# PowerModule.net
KiCad netlist of a schematic drawn in EAGLE
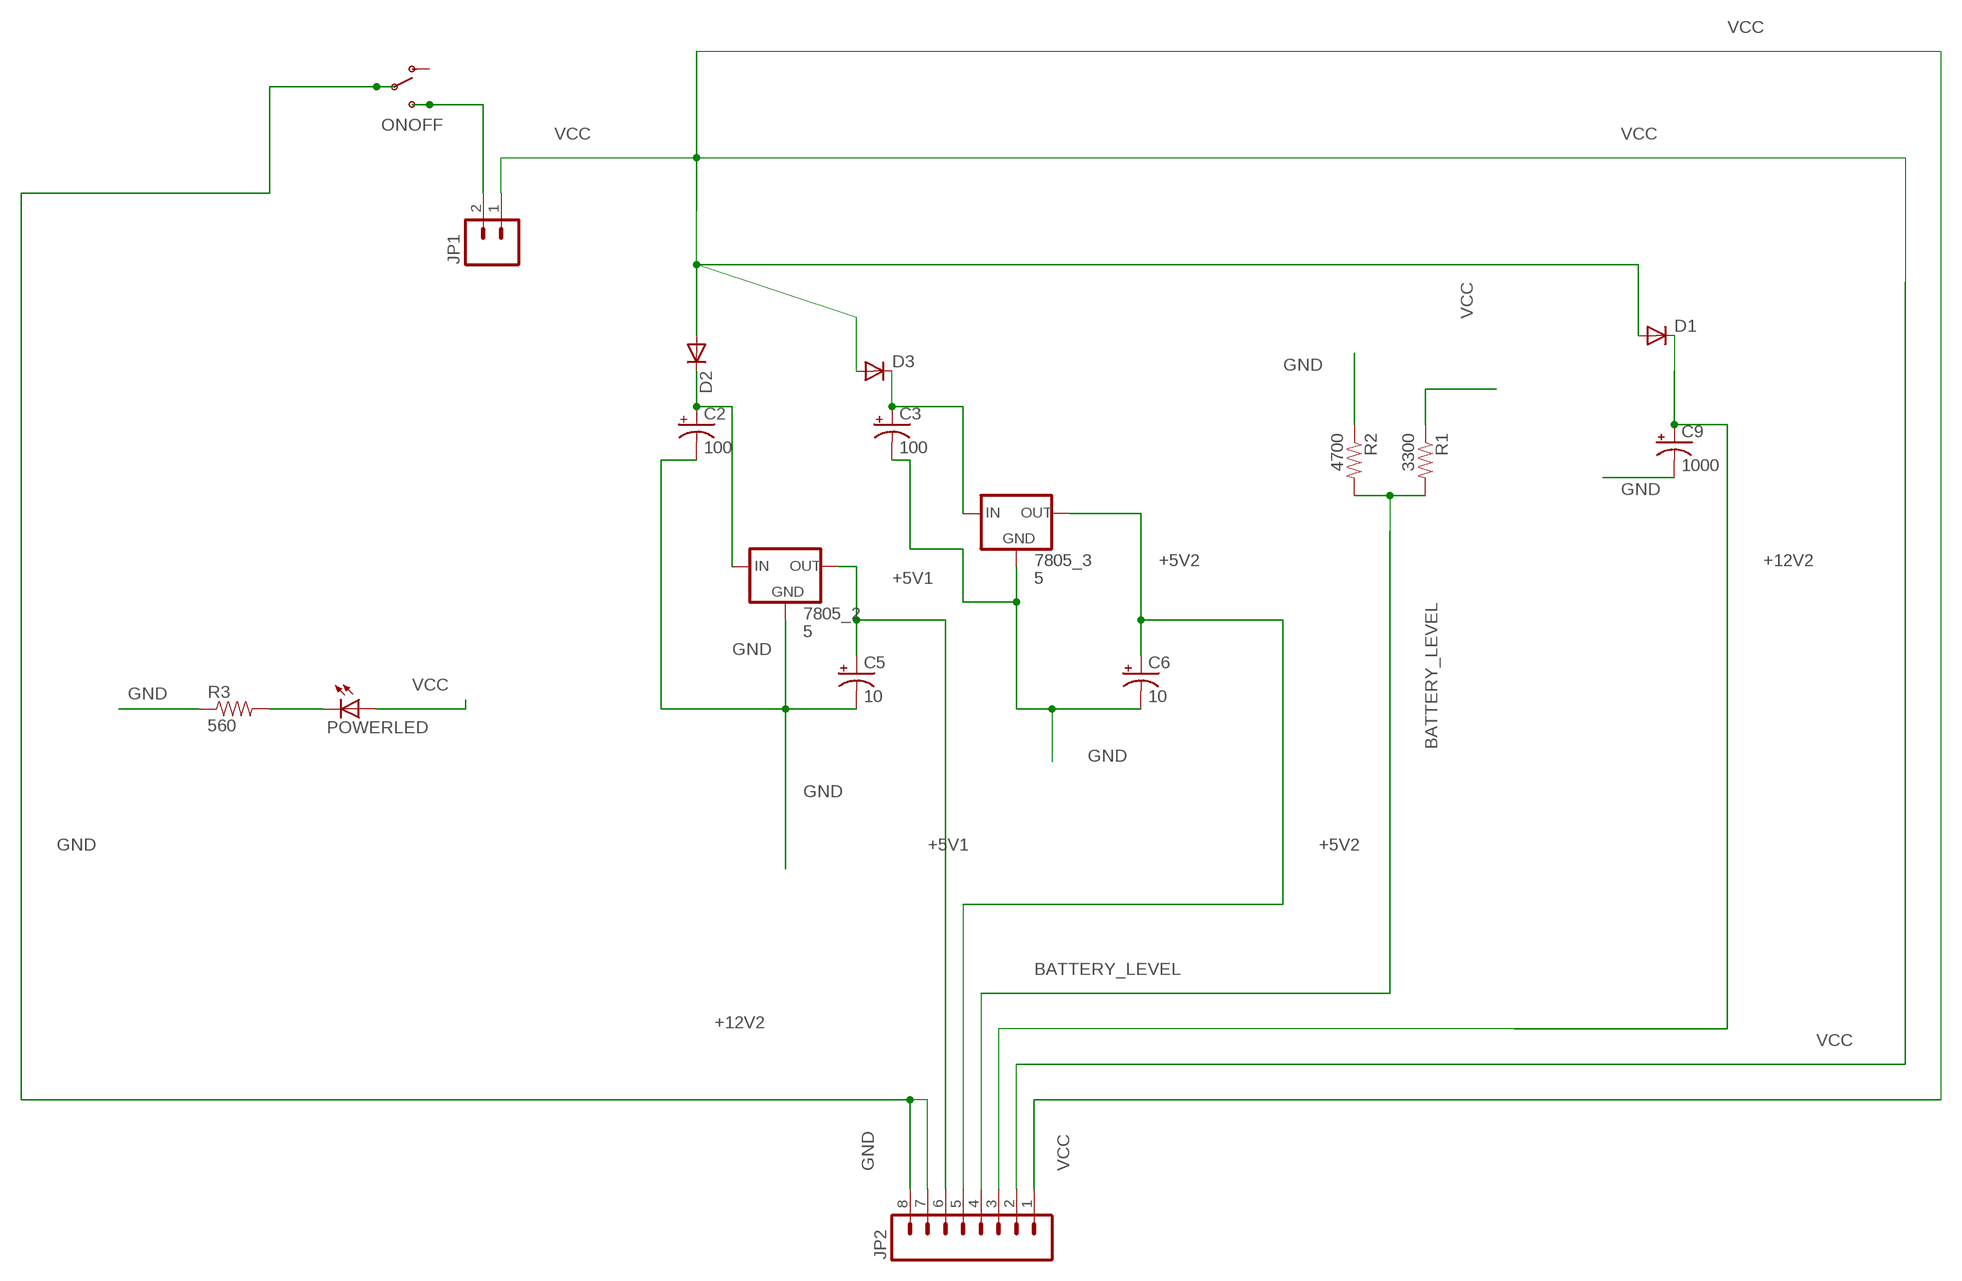
[diagram p0: schematic, sheet 1]

(export (version "E")
  (design (tool "Eeschema 10.0.6"))
  (components
    (comp (ref "7805_2")
      (value "5")
      (footprint "eagle-import:TO220-IGO")
      (libsource (lib "eagle-import") (part "V_REG_78XXSINK"))
    )
    (comp (ref "7805_3")
      (value "5")
      (footprint "eagle-import:TO220-IGO")
      (libsource (lib "eagle-import") (part "V_REG_78XXSINK"))
    )
    (comp (ref "C2")
      (value "100")
      (footprint "eagle-import:CPOL-RADIAL-100UF-25V")
      (libsource (lib "eagle-import") (part "CAP_POLPTH1"))
    )
    (comp (ref "C3")
      (value "100")
      (footprint "eagle-import:CPOL-RADIAL-100UF-25V")
      (libsource (lib "eagle-import") (part "CAP_POLPTH1"))
    )
    (comp (ref "C5")
      (value "10")
      (footprint "eagle-import:CPOL-RADIAL-10UF-25V")
      (libsource (lib "eagle-import") (part "CAP_POLPTH2"))
    )
    (comp (ref "C6")
      (value "10")
      (footprint "eagle-import:CPOL-RADIAL-10UF-25V")
      (libsource (lib "eagle-import") (part "CAP_POLPTH2"))
    )
    (comp (ref "C9")
      (value "1000")
      (footprint "eagle-import:CPOL-RADIAL-100UF-25V")
      (libsource (lib "eagle-import") (part "CAP_POLPTH1"))
    )
    (comp (ref "D1")
      (value "DIODEPTH")
      (footprint "eagle-import:DIODE-1N4001")
      (libsource (lib "eagle-import") (part "DIODEPTH"))
    )
    (comp (ref "D2")
      (value "DIODEPTH")
      (footprint "eagle-import:DIODE-1N4001")
      (libsource (lib "eagle-import") (part "DIODEPTH"))
    )
    (comp (ref "D3")
      (value "DIODEPTH")
      (footprint "eagle-import:DIODE-1N4001")
      (libsource (lib "eagle-import") (part "DIODEPTH"))
    )
    (comp (ref "JP1")
      (value "M025MM")
      (footprint "eagle-import:SCREWTERMINAL-5MM-2")
      (libsource (lib "eagle-import") (part "M025MM"))
    )
    (comp (ref "JP2")
      (value "M081X08")
      (footprint "eagle-import:1X08")
      (libsource (lib "eagle-import") (part "M081X08"))
    )
    (comp (ref "ONOFF")
      (value "SWITCH-SPSTPTH")
      (footprint "eagle-import:SWITCH-SPDT")
      (libsource (lib "eagle-import") (part "SWITCH-SPSTPTH"))
    )
    (comp (ref "POWERLED")
      (value "LED3MM")
      (footprint "eagle-import:LED3MM")
      (libsource (lib "eagle-import") (part "LED3MM"))
    )
    (comp (ref "R1")
      (value "3300")
      (footprint "eagle-import:AXIAL-0.4")
      (libsource (lib "eagle-import") (part "RESISTORPTH-1/4W"))
    )
    (comp (ref "R2")
      (value "4700")
      (footprint "eagle-import:AXIAL-0.4")
      (libsource (lib "eagle-import") (part "RESISTORPTH-1/4W"))
    )
    (comp (ref "R3")
      (value "560")
      (footprint "eagle-import:AXIAL-0.4")
      (libsource (lib "eagle-import") (part "RESISTORPTH-1/4W"))
    )
  )
  (nets
    (net (code "1") (name "/+5V1") (class "Default")
      (node (ref "7805_2") (pin "OUT") (pinfunction "OUT_OUT") (pintype "output"))
      (node (ref "C5") (pin "1") (pinfunction "+_1") (pintype "passive"))
      (node (ref "JP2") (pin "6") (pinfunction "6_6") (pintype "passive"))
    )
    (net (code "2") (name "/+5V2") (class "Default")
      (node (ref "7805_3") (pin "OUT") (pinfunction "OUT_OUT") (pintype "output"))
      (node (ref "C6") (pin "1") (pinfunction "+_1") (pintype "passive"))
      (node (ref "JP2") (pin "5") (pinfunction "5_5") (pintype "passive"))
    )
    (net (code "3") (name "/+12V2") (class "Default")
      (node (ref "C9") (pin "1") (pinfunction "+_1") (pintype "passive"))
      (node (ref "D1") (pin "C") (pinfunction "C_C") (pintype "passive"))
      (node (ref "JP2") (pin "3") (pinfunction "3_3") (pintype "passive"))
    )
    (net (code "4") (name "/BATTERY_LEVEL") (class "Default")
      (node (ref "JP2") (pin "4") (pinfunction "4_4") (pintype "passive"))
      (node (ref "R1") (pin "P$2") (pinfunction "2_P$2") (pintype "passive"))
      (node (ref "R2") (pin "P$2") (pinfunction "2_P$2") (pintype "passive"))
    )
    (net (code "5") (name "/GND") (class "Default")
      (node (ref "7805_2") (pin "GND") (pinfunction "GND_GND") (pintype "input"))
      (node (ref "7805_3") (pin "GND") (pinfunction "GND_GND") (pintype "input"))
      (node (ref "C2") (pin "2") (pinfunction "-_2") (pintype "passive"))
      (node (ref "C3") (pin "2") (pinfunction "-_2") (pintype "passive"))
      (node (ref "C5") (pin "2") (pinfunction "-_2") (pintype "passive"))
      (node (ref "C6") (pin "2") (pinfunction "-_2") (pintype "passive"))
      (node (ref "C9") (pin "2") (pinfunction "-_2") (pintype "passive"))
      (node (ref "JP2") (pin "7") (pinfunction "7_7") (pintype "passive"))
      (node (ref "JP2") (pin "8") (pinfunction "8_8") (pintype "passive"))
      (node (ref "ONOFF") (pin "2") (pinfunction "P_2") (pintype "passive"))
      (node (ref "R2") (pin "P$1") (pinfunction "1_P$1") (pintype "passive"))
      (node (ref "R3") (pin "P$1") (pinfunction "1_P$1") (pintype "passive"))
    )
    (net (code "6") (name "/VCC") (class "Default")
      (node (ref "D1") (pin "A") (pinfunction "A_A") (pintype "passive"))
      (node (ref "D2") (pin "A") (pinfunction "A_A") (pintype "passive"))
      (node (ref "D3") (pin "A") (pinfunction "A_A") (pintype "passive"))
      (node (ref "JP1") (pin "1") (pinfunction "1_1") (pintype "passive"))
      (node (ref "JP2") (pin "1") (pinfunction "1_1") (pintype "passive"))
      (node (ref "JP2") (pin "2") (pinfunction "2_2") (pintype "passive"))
      (node (ref "POWERLED") (pin "A") (pinfunction "A_A") (pintype "passive"))
      (node (ref "R1") (pin "P$1") (pinfunction "1_P$1") (pintype "passive"))
    )
    (net (code "7") (name "Net-(C2-+)") (class "Default")
      (node (ref "7805_2") (pin "IN") (pinfunction "IN_IN") (pintype "input"))
      (node (ref "C2") (pin "1") (pinfunction "+_1") (pintype "passive"))
      (node (ref "D2") (pin "C") (pinfunction "C_C") (pintype "passive"))
    )
    (net (code "8") (name "Net-(C3-+)") (class "Default")
      (node (ref "7805_3") (pin "IN") (pinfunction "IN_IN") (pintype "input"))
      (node (ref "C3") (pin "1") (pinfunction "+_1") (pintype "passive"))
      (node (ref "D3") (pin "C") (pinfunction "C_C") (pintype "passive"))
    )
    (net (code "9") (name "Net-(ONOFF-S)") (class "Default")
      (node (ref "JP1") (pin "2") (pinfunction "2_2") (pintype "passive"))
      (node (ref "ONOFF") (pin "3") (pinfunction "S_3") (pintype "passive"))
    )
    (net (code "10") (name "Net-(POWERLED-C)") (class "Default")
      (node (ref "POWERLED") (pin "K") (pinfunction "C_K") (pintype "passive"))
      (node (ref "R3") (pin "P$2") (pinfunction "2_P$2") (pintype "passive"))
    )
    (net (code "11") (name "unconnected-(ONOFF-O-Pad1)") (class "Default")
      (node (ref "ONOFF") (pin "1") (pinfunction "O_1") (pintype "passive"))
    )
  )
)
